# Motor_Driver_ClearanceIssues.net
KiCad netlist of a schematic drawn in EAGLE
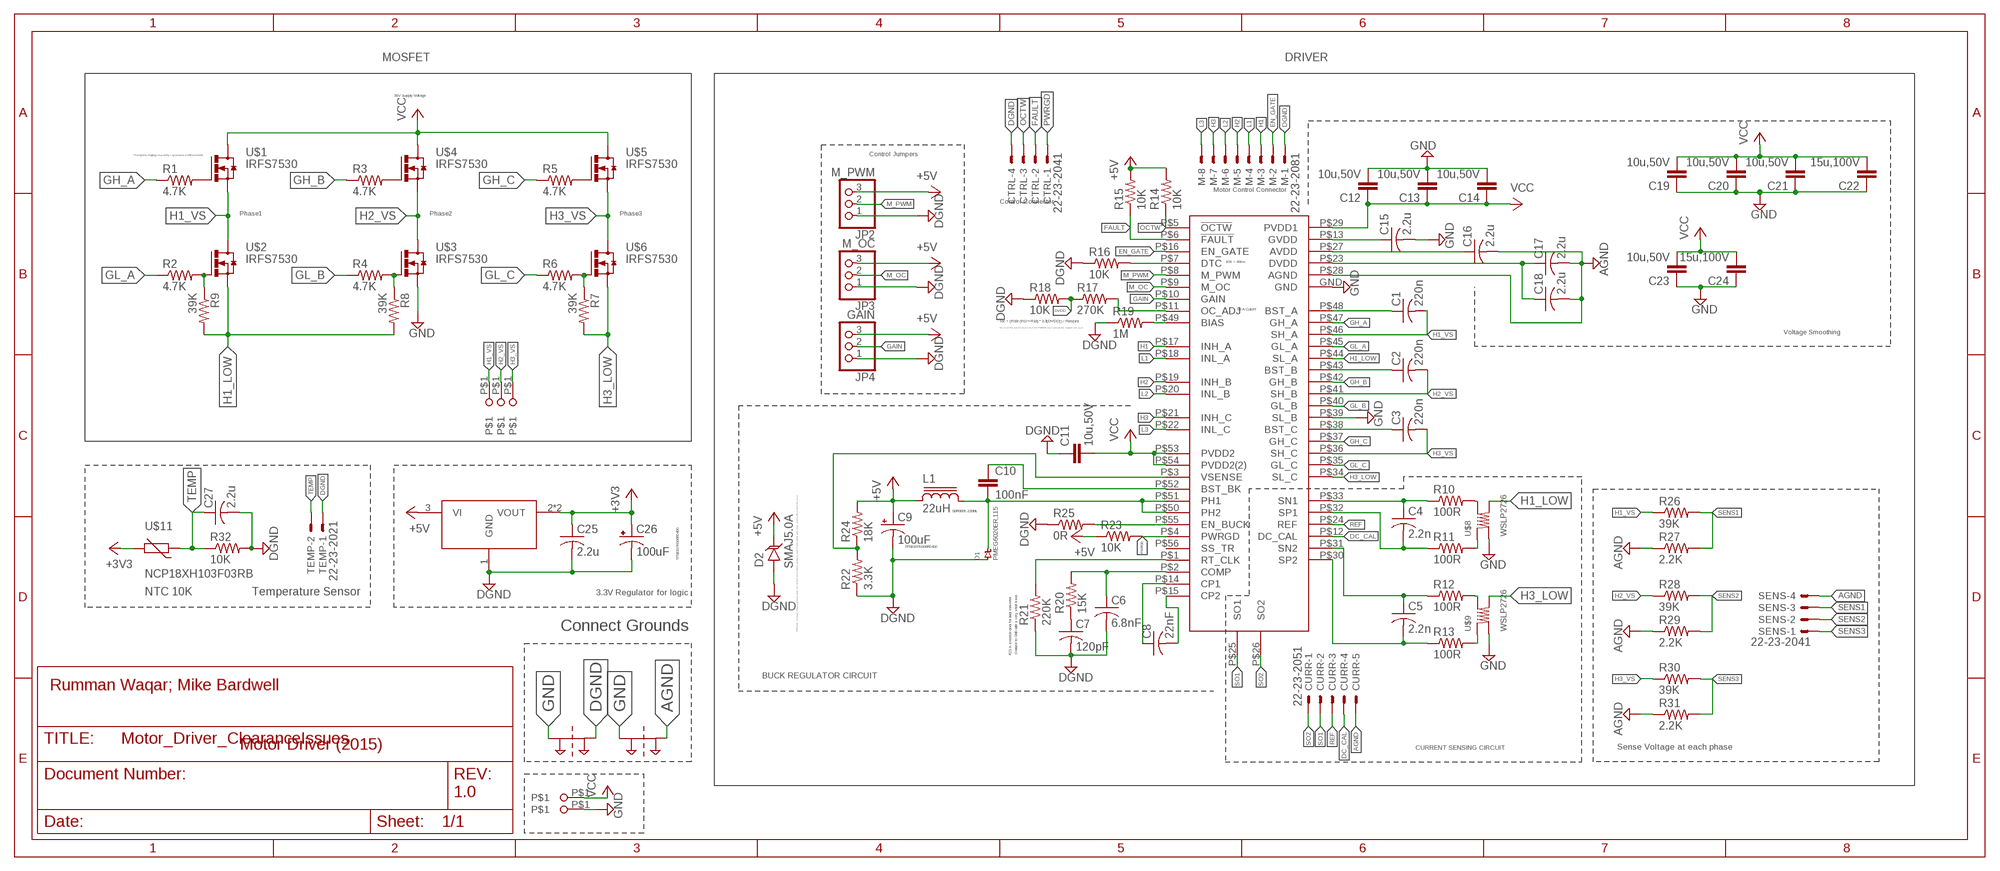
[diagram p0: schematic, sheet 1]

(export (version "E")
  (design (tool "Eeschema 10.0.6"))
  (components
    (comp (ref "C1")
      (value "220n")
      (footprint "eagle-import:C0805")
      (libsource (lib "eagle-import") (part "C-USC0805"))
    )
    (comp (ref "C2")
      (value "220n")
      (footprint "eagle-import:C0805")
      (libsource (lib "eagle-import") (part "C-USC0805"))
    )
    (comp (ref "C3")
      (value "220n")
      (footprint "eagle-import:C0805")
      (libsource (lib "eagle-import") (part "C-USC0805"))
    )
    (comp (ref "C4")
      (value "2.2n")
      (footprint "eagle-import:C0603")
      (libsource (lib "eagle-import") (part "C-USC0603"))
    )
    (comp (ref "C5")
      (value "2.2n")
      (footprint "eagle-import:C0603")
      (libsource (lib "eagle-import") (part "C-USC0603"))
    )
    (comp (ref "C6")
      (value "6.8nF")
      (footprint "eagle-import:C0603")
      (libsource (lib "eagle-import") (part "C-USC0603"))
    )
    (comp (ref "C7")
      (value "120pF")
      (footprint "eagle-import:C0603")
      (libsource (lib "eagle-import") (part "C-USC0603"))
    )
    (comp (ref "C8")
      (value "22nF")
      (footprint "eagle-import:C0603")
      (libsource (lib "eagle-import") (part "C-USC0603"))
    )
    (comp (ref "C9")
      (value "100uF")
      (footprint "eagle-import:EIA3528-KIT")
      (libsource (lib "eagle-import") (part "CAP_POL3528-KIT"))
    )
    (comp (ref "C10")
      (value "100nF")
      (footprint "eagle-import:0805")
      (libsource (lib "eagle-import") (part "CAP0805"))
    )
    (comp (ref "C11")
      (value "10u,50V")
      (footprint "eagle-import:1206")
      (libsource (lib "eagle-import") (part "CAP1206"))
    )
    (comp (ref "C12")
      (value "10u,50V")
      (footprint "eagle-import:1206")
      (libsource (lib "eagle-import") (part "CAP1206"))
    )
    (comp (ref "C13")
      (value "10u,50V")
      (footprint "eagle-import:1206")
      (libsource (lib "eagle-import") (part "CAP1206"))
    )
    (comp (ref "C14")
      (value "10u,50V")
      (footprint "eagle-import:1206")
      (libsource (lib "eagle-import") (part "CAP1206"))
    )
    (comp (ref "C15")
      (value "2.2u")
      (footprint "eagle-import:C0805")
      (libsource (lib "eagle-import") (part "C-USC0805"))
    )
    (comp (ref "C16")
      (value "2.2u")
      (footprint "eagle-import:C0805")
      (libsource (lib "eagle-import") (part "C-USC0805"))
    )
    (comp (ref "C17")
      (value "2.2u")
      (footprint "eagle-import:C0805")
      (libsource (lib "eagle-import") (part "C-USC0805"))
    )
    (comp (ref "C18")
      (value "2.2u")
      (footprint "eagle-import:C0805")
      (libsource (lib "eagle-import") (part "C-USC0805"))
    )
    (comp (ref "C19")
      (value "10u,50V")
      (footprint "eagle-import:1206")
      (libsource (lib "eagle-import") (part "CAP1206"))
    )
    (comp (ref "C20")
      (value "10u,50V")
      (footprint "eagle-import:1206")
      (libsource (lib "eagle-import") (part "CAP1206"))
    )
    (comp (ref "C21")
      (value "10u,50V")
      (footprint "eagle-import:1206")
      (libsource (lib "eagle-import") (part "CAP1206"))
    )
    (comp (ref "C22")
      (value "15u,100V")
      (footprint "eagle-import:C2220K")
      (libsource (lib "eagle-import") (part "C-EUC2220K"))
    )
    (comp (ref "C23")
      (value "10u,50V")
      (footprint "eagle-import:1206")
      (libsource (lib "eagle-import") (part "CAP1206"))
    )
    (comp (ref "C24")
      (value "15u,100V")
      (footprint "eagle-import:C2220K")
      (libsource (lib "eagle-import") (part "C-EUC2220K"))
    )
    (comp (ref "C25")
      (value "2.2u")
      (footprint "eagle-import:C0805")
      (libsource (lib "eagle-import") (part "C-USC0805"))
    )
    (comp (ref "C26")
      (value "100uF")
      (footprint "eagle-import:EIA3528-KIT")
      (libsource (lib "eagle-import") (part "CAP_POL3528-KIT"))
    )
    (comp (ref "C27")
      (value "2.2u")
      (footprint "eagle-import:C0805")
      (libsource (lib "eagle-import") (part "C-USC0805"))
    )
    (comp (ref "CTRL")
      (value "22-23-2041")
      (footprint "eagle-import:22-23-2041")
      (fields (field (name "MF") "MOLEX"))
      (libsource (lib "eagle-import") (part "22-23-2041"))
    )
    (comp (ref "CURR")
      (value "22-23-2051")
      (footprint "eagle-import:22-23-2051")
      (fields (field (name "MF") "MOLEX"))
      (libsource (lib "eagle-import") (part "22-23-2051"))
    )
    (comp (ref "D1")
      (value "PMEG6020ER,115")
      (footprint "eagle-import:SOD123W")
      (libsource (lib "eagle-import") (part "DIODE[SCHOTKY]-SOD123W"))
    )
    (comp (ref "D2")
      (value "SMAJ5.0A")
      (footprint "eagle-import:SMA-DIODE")
      (libsource (lib "eagle-import") (part "TVSSMA"))
    )
    (comp (ref "JP2")
      (value "M_PWM")
      (footprint "eagle-import:1X03")
      (libsource (lib "eagle-import") (part "PINHD-1X3"))
    )
    (comp (ref "JP3")
      (value "M_OC")
      (footprint "eagle-import:1X03")
      (libsource (lib "eagle-import") (part "PINHD-1X3"))
    )
    (comp (ref "JP4")
      (value "GAIN")
      (footprint "eagle-import:1X03")
      (libsource (lib "eagle-import") (part "PINHD-1X3"))
    )
    (comp (ref "L1")
      (value "22uH")
      (footprint "eagle-import:SDR0805")
      (libsource (lib "eagle-import") (part "SDR0805"))
    )
    (comp (ref "M")
      (value "22-23-2081")
      (footprint "eagle-import:22-23-2081")
      (fields (field (name "MF") "MOLEX"))
      (libsource (lib "eagle-import") (part "22-23-2081"))
    )
    (comp (ref "PT1")
      (value "2PT_GND_TIE")
      (footprint "eagle-import:2PT_GND_TIE")
      (libsource (lib "eagle-import") (part "2PT_GND_TIE"))
    )
    (comp (ref "PT2")
      (value "2PT_GND_TIE")
      (footprint "eagle-import:2PT_GND_TIE")
      (libsource (lib "eagle-import") (part "2PT_GND_TIE"))
    )
    (comp (ref "R1")
      (value "4.7K")
      (footprint "eagle-import:R0603")
      (libsource (lib "eagle-import") (part "R-US_R0603"))
    )
    (comp (ref "R2")
      (value "4.7K")
      (footprint "eagle-import:R0603")
      (libsource (lib "eagle-import") (part "R-US_R0603"))
    )
    (comp (ref "R3")
      (value "4.7K")
      (footprint "eagle-import:R0603")
      (libsource (lib "eagle-import") (part "R-US_R0603"))
    )
    (comp (ref "R4")
      (value "4.7K")
      (footprint "eagle-import:R0603")
      (libsource (lib "eagle-import") (part "R-US_R0603"))
    )
    (comp (ref "R5")
      (value "4.7K")
      (footprint "eagle-import:R0603")
      (libsource (lib "eagle-import") (part "R-US_R0603"))
    )
    (comp (ref "R6")
      (value "4.7K")
      (footprint "eagle-import:R0603")
      (libsource (lib "eagle-import") (part "R-US_R0603"))
    )
    (comp (ref "R7")
      (value "39K")
      (footprint "eagle-import:R0603")
      (libsource (lib "eagle-import") (part "R-US_R0603"))
    )
    (comp (ref "R8")
      (value "39K")
      (footprint "eagle-import:R0603")
      (libsource (lib "eagle-import") (part "R-US_R0603"))
    )
    (comp (ref "R9")
      (value "39K")
      (footprint "eagle-import:R0603")
      (libsource (lib "eagle-import") (part "R-US_R0603"))
    )
    (comp (ref "R10")
      (value "100R")
      (footprint "eagle-import:R0603")
      (libsource (lib "eagle-import") (part "R-US_R0603"))
    )
    (comp (ref "R11")
      (value "100R")
      (footprint "eagle-import:R0603")
      (libsource (lib "eagle-import") (part "R-US_R0603"))
    )
    (comp (ref "R12")
      (value "100R")
      (footprint "eagle-import:R0603")
      (libsource (lib "eagle-import") (part "R-US_R0603"))
    )
    (comp (ref "R13")
      (value "100R")
      (footprint "eagle-import:R0603")
      (libsource (lib "eagle-import") (part "R-US_R0603"))
    )
    (comp (ref "R14")
      (value "10K")
      (footprint "eagle-import:R0603")
      (libsource (lib "eagle-import") (part "R-US_R0603"))
    )
    (comp (ref "R15")
      (value "10K")
      (footprint "eagle-import:R0603")
      (libsource (lib "eagle-import") (part "R-US_R0603"))
    )
    (comp (ref "R16")
      (value "10K")
      (footprint "eagle-import:R0603")
      (libsource (lib "eagle-import") (part "R-US_R0603"))
    )
    (comp (ref "R17")
      (value "270K")
      (footprint "eagle-import:R0603")
      (libsource (lib "eagle-import") (part "R-US_R0603"))
    )
    (comp (ref "R18")
      (value "10K")
      (footprint "eagle-import:R0603")
      (libsource (lib "eagle-import") (part "R-US_R0603"))
    )
    (comp (ref "R19")
      (value "1M")
      (footprint "eagle-import:R0603")
      (libsource (lib "eagle-import") (part "R-US_R0603"))
    )
    (comp (ref "R20")
      (value "15K")
      (footprint "eagle-import:R0603")
      (libsource (lib "eagle-import") (part "R-US_R0603"))
    )
    (comp (ref "R21")
      (value "220K")
      (footprint "eagle-import:R0603")
      (libsource (lib "eagle-import") (part "R-US_R0603"))
    )
    (comp (ref "R22")
      (value "3.3K")
      (footprint "eagle-import:R0603")
      (libsource (lib "eagle-import") (part "R-US_R0603"))
    )
    (comp (ref "R23")
      (value "10K")
      (footprint "eagle-import:R0603")
      (libsource (lib "eagle-import") (part "R-US_R0603"))
    )
    (comp (ref "R24")
      (value "18K")
      (footprint "eagle-import:R0603")
      (libsource (lib "eagle-import") (part "R-US_R0603"))
    )
    (comp (ref "R25")
      (value "0R")
      (footprint "eagle-import:R0603")
      (libsource (lib "eagle-import") (part "R-US_R0603"))
    )
    (comp (ref "R26")
      (value "39K")
      (footprint "eagle-import:R0805")
      (libsource (lib "eagle-import") (part "R-US_R0805"))
    )
    (comp (ref "R27")
      (value "2.2K")
      (footprint "eagle-import:R0805")
      (libsource (lib "eagle-import") (part "R-US_R0805"))
    )
    (comp (ref "R28")
      (value "39K")
      (footprint "eagle-import:R0805")
      (libsource (lib "eagle-import") (part "R-US_R0805"))
    )
    (comp (ref "R29")
      (value "2.2K")
      (footprint "eagle-import:R0805")
      (libsource (lib "eagle-import") (part "R-US_R0805"))
    )
    (comp (ref "R30")
      (value "39K")
      (footprint "eagle-import:R0805")
      (libsource (lib "eagle-import") (part "R-US_R0805"))
    )
    (comp (ref "R31")
      (value "2.2K")
      (footprint "eagle-import:R0805")
      (libsource (lib "eagle-import") (part "R-US_R0805"))
    )
    (comp (ref "R32")
      (value "10K")
      (footprint "eagle-import:M0805")
      (libsource (lib "eagle-import") (part "R-US_M0805"))
    )
    (comp (ref "SENS")
      (value "22-23-2041")
      (footprint "eagle-import:22-23-2041")
      (fields (field (name "MF") "MOLEX"))
      (libsource (lib "eagle-import") (part "22-23-2041"))
    )
    (comp (ref "TEMP")
      (value "22-23-2021")
      (footprint "eagle-import:22-23-2021")
      (fields (field (name "MF") "MOLEX"))
      (libsource (lib "eagle-import") (part "22-23-2021"))
    )
    (comp (ref "U$1")
      (value "IRFS7530")
      (footprint "eagle-import:IRF7530_HEATSINK")
      (libsource (lib "eagle-import") (part "IRFS7530_HEATSINK"))
    )
    (comp (ref "U$2")
      (value "IRFS7530")
      (footprint "eagle-import:IRF7530_HEATSINK")
      (libsource (lib "eagle-import") (part "IRFS7530_HEATSINK"))
    )
    (comp (ref "U$3")
      (value "IRFS7530")
      (footprint "eagle-import:IRF7530_HEATSINK")
      (libsource (lib "eagle-import") (part "IRFS7530_HEATSINK"))
    )
    (comp (ref "U$4")
      (value "IRFS7530")
      (footprint "eagle-import:IRF7530_HEATSINK")
      (libsource (lib "eagle-import") (part "IRFS7530_HEATSINK"))
    )
    (comp (ref "U$5")
      (value "IRFS7530")
      (footprint "eagle-import:IRF7530_HEATSINK")
      (libsource (lib "eagle-import") (part "IRFS7530_HEATSINK"))
    )
    (comp (ref "U$6")
      (value "IRFS7530")
      (footprint "eagle-import:IRF7530_HEATSINK")
      (libsource (lib "eagle-import") (part "IRFS7530_HEATSINK"))
    )
    (comp (ref "U$7")
      (value "DRV8302")
      (footprint "eagle-import:DRV8302")
      (libsource (lib "eagle-import") (part "DRV8302"))
    )
    (comp (ref "U$8")
      (value "WSLP2726")
      (footprint "eagle-import:WSLP2726")
      (libsource (lib "eagle-import") (part "WSLP2726"))
    )
    (comp (ref "U$9")
      (value "WSLP2726")
      (footprint "eagle-import:WSLP2726")
      (libsource (lib "eagle-import") (part "WSLP2726"))
    )
    (comp (ref "U$10")
      (value "TC2117")
      (footprint "eagle-import:SOT223")
      (libsource (lib "eagle-import") (part "TC2117"))
    )
    (comp (ref "U$11")
      (value "NCP18XH103F03RB")
      (footprint "eagle-import:R0603")
      (libsource (lib "eagle-import") (part "NCP18XH103F03RB"))
    )
    (comp (ref "U$12")
      (value "1CONN_SOLDER")
      (footprint "eagle-import:1CONN_PAD")
      (libsource (lib "eagle-import") (part "1CONN_SOLDER"))
    )
    (comp (ref "U$13")
      (value "1CONN_SOLDER")
      (footprint "eagle-import:1CONN_PAD")
      (libsource (lib "eagle-import") (part "1CONN_SOLDER"))
    )
    (comp (ref "U$14")
      (value "1CONN_SOLDER")
      (footprint "eagle-import:1CONN_PAD")
      (libsource (lib "eagle-import") (part "1CONN_SOLDER"))
    )
    (comp (ref "U$15")
      (value "1CONN_SOLDER")
      (footprint "eagle-import:1CONN_PAD")
      (libsource (lib "eagle-import") (part "1CONN_SOLDER"))
    )
    (comp (ref "U$16")
      (value "1CONN_SOLDER")
      (footprint "eagle-import:1CONN_PAD")
      (libsource (lib "eagle-import") (part "1CONN_SOLDER"))
    )
  )
  (nets
    (net (code "1") (name "+3V3") (class "Default")
      (node (ref "C25") (pin "1") (pinfunction "1_1") (pintype "passive"))
      (node (ref "C26") (pin "A") (pinfunction "+_A") (pintype "passive"))
      (node (ref "U$10") (pin "2") (pinfunction "VOUT_2") (pintype "bidirectional"))
      (node (ref "U$10") (pin "4") (pinfunction "VOUT_4") (pintype "bidirectional"))
      (node (ref "U$11") (pin "2") (pinfunction "2_2") (pintype "passive"))
    )
    (net (code "2") (name "+5V") (class "Default")
      (node (ref "C9") (pin "A") (pinfunction "+_A") (pintype "passive"))
      (node (ref "D2") (pin "C") (pinfunction "C_C") (pintype "passive"))
      (node (ref "JP2") (pin "3") (pinfunction "3_3") (pintype "passive"))
      (node (ref "JP3") (pin "3") (pinfunction "3_3") (pintype "passive"))
      (node (ref "JP4") (pin "3") (pinfunction "3_3") (pintype "passive"))
      (node (ref "L1") (pin "1") (pinfunction "1_1") (pintype "passive"))
      (node (ref "R14") (pin "2") (pinfunction "2_2") (pintype "passive"))
      (node (ref "R15") (pin "2") (pinfunction "2_2") (pintype "passive"))
      (node (ref "R23") (pin "1") (pinfunction "1_1") (pintype "passive"))
      (node (ref "R24") (pin "2") (pinfunction "2_2") (pintype "passive"))
      (node (ref "U$10") (pin "3") (pinfunction "VI_3") (pintype "bidirectional"))
    )
    (net (code "3") (name "AGND") (class "Default")
      (node (ref "C16") (pin "2") (pinfunction "2_2") (pintype "passive"))
      (node (ref "C17") (pin "2") (pinfunction "2_2") (pintype "passive"))
      (node (ref "C18") (pin "2") (pinfunction "2_2") (pintype "passive"))
      (node (ref "CURR") (pin "5") (pinfunction "S_5") (pintype "passive"))
      (node (ref "PT2") (pin "P$2") (pinfunction "P$2_P$2") (pintype "bidirectional"))
      (node (ref "R27") (pin "1") (pinfunction "1_1") (pintype "passive"))
      (node (ref "R29") (pin "1") (pinfunction "1_1") (pintype "passive"))
      (node (ref "R31") (pin "1") (pinfunction "1_1") (pintype "passive"))
      (node (ref "SENS") (pin "4") (pinfunction "S_4") (pintype "passive"))
      (node (ref "U$7") (pin "P$28") (pinfunction "AGND_P$28") (pintype "bidirectional"))
    )
    (net (code "4") (name "DC_CAL") (class "Default")
      (node (ref "CURR") (pin "4") (pinfunction "S_4") (pintype "passive"))
      (node (ref "U$7") (pin "P$12") (pinfunction "DC_CAL_P$12") (pintype "bidirectional"))
    )
    (net (code "5") (name "DGND") (class "Default")
      (node (ref "C11") (pin "1") (pinfunction "1_1") (pintype "passive"))
      (node (ref "C25") (pin "2") (pinfunction "2_2") (pintype "passive"))
      (node (ref "C26") (pin "C") (pinfunction "-_C") (pintype "passive"))
      (node (ref "C27") (pin "2") (pinfunction "2_2") (pintype "passive"))
      (node (ref "C6") (pin "2") (pinfunction "2_2") (pintype "passive"))
      (node (ref "C7") (pin "2") (pinfunction "2_2") (pintype "passive"))
      (node (ref "C9") (pin "C") (pinfunction "-_C") (pintype "passive"))
      (node (ref "CTRL") (pin "4") (pinfunction "S_4") (pintype "passive"))
      (node (ref "D1") (pin "P$1") (pinfunction "1_P$1") (pintype "bidirectional"))
      (node (ref "D2") (pin "A") (pinfunction "A_A") (pintype "passive"))
      (node (ref "JP2") (pin "1") (pinfunction "1_1") (pintype "passive"))
      (node (ref "JP3") (pin "1") (pinfunction "1_1") (pintype "passive"))
      (node (ref "JP4") (pin "1") (pinfunction "1_1") (pintype "passive"))
      (node (ref "M") (pin "1") (pinfunction "S_1") (pintype "passive"))
      (node (ref "PT1") (pin "P$2") (pinfunction "P$2_P$2") (pintype "bidirectional"))
      (node (ref "R16") (pin "1") (pinfunction "1_1") (pintype "passive"))
      (node (ref "R18") (pin "1") (pinfunction "1_1") (pintype "passive"))
      (node (ref "R19") (pin "1") (pinfunction "1_1") (pintype "passive"))
      (node (ref "R21") (pin "1") (pinfunction "1_1") (pintype "passive"))
      (node (ref "R22") (pin "1") (pinfunction "1_1") (pintype "passive"))
      (node (ref "R25") (pin "1") (pinfunction "1_1") (pintype "passive"))
      (node (ref "R32") (pin "2") (pinfunction "2_2") (pintype "passive"))
      (node (ref "TEMP") (pin "1") (pinfunction "S_1") (pintype "passive"))
      (node (ref "U$10") (pin "1") (pinfunction "GND_1") (pintype "bidirectional"))
    )
    (net (code "6") (name "DVDD") (class "Default")
      (node (ref "R17") (pin "1") (pinfunction "1_1") (pintype "passive"))
      (node (ref "R18") (pin "2") (pinfunction "2_2") (pintype "passive"))
    )
    (net (code "7") (name "EN_GATE") (class "Default")
      (node (ref "M") (pin "2") (pinfunction "S_2") (pintype "passive"))
      (node (ref "U$7") (pin "P$16") (pinfunction "EN_GATE_P$16") (pintype "bidirectional"))
    )
    (net (code "8") (name "FAULT") (class "Default")
      (node (ref "CTRL") (pin "2") (pinfunction "S_2") (pintype "passive"))
      (node (ref "R15") (pin "1") (pinfunction "1_1") (pintype "passive"))
      (node (ref "U$7") (pin "P$6") (pinfunction "~{FAULT}_P$6") (pintype "bidirectional"))
    )
    (net (code "9") (name "GAIN") (class "Default")
      (node (ref "JP4") (pin "2") (pinfunction "2_2") (pintype "passive"))
      (node (ref "U$7") (pin "P$10") (pinfunction "GAIN_P$10") (pintype "bidirectional"))
    )
    (net (code "10") (name "GH_A") (class "Default")
      (node (ref "R1") (pin "1") (pinfunction "1_1") (pintype "passive"))
      (node (ref "U$7") (pin "P$47") (pinfunction "GH_A_P$47") (pintype "bidirectional"))
    )
    (net (code "11") (name "GH_B") (class "Default")
      (node (ref "R3") (pin "1") (pinfunction "1_1") (pintype "passive"))
      (node (ref "U$7") (pin "P$42") (pinfunction "GH_B_P$42") (pintype "bidirectional"))
    )
    (net (code "12") (name "GH_C") (class "Default")
      (node (ref "R5") (pin "1") (pinfunction "1_1") (pintype "passive"))
      (node (ref "U$7") (pin "P$37") (pinfunction "GH_C_P$37") (pintype "bidirectional"))
    )
    (net (code "13") (name "GL_A") (class "Default")
      (node (ref "R2") (pin "1") (pinfunction "1_1") (pintype "passive"))
      (node (ref "U$7") (pin "P$45") (pinfunction "GL_A_P$45") (pintype "bidirectional"))
    )
    (net (code "14") (name "GL_B") (class "Default")
      (node (ref "R4") (pin "1") (pinfunction "1_1") (pintype "passive"))
      (node (ref "U$7") (pin "P$40") (pinfunction "GL_B_P$40") (pintype "bidirectional"))
    )
    (net (code "15") (name "GL_C") (class "Default")
      (node (ref "R6") (pin "1") (pinfunction "1_1") (pintype "passive"))
      (node (ref "U$7") (pin "P$35") (pinfunction "GL_C_P$35") (pintype "bidirectional"))
    )
    (net (code "16") (name "GND") (class "Default")
      (node (ref "C12") (pin "2") (pinfunction "2_2") (pintype "passive"))
      (node (ref "C13") (pin "2") (pinfunction "2_2") (pintype "passive"))
      (node (ref "C14") (pin "2") (pinfunction "2_2") (pintype "passive"))
      (node (ref "C15") (pin "2") (pinfunction "2_2") (pintype "passive"))
      (node (ref "C19") (pin "1") (pinfunction "1_1") (pintype "passive"))
      (node (ref "C20") (pin "1") (pinfunction "1_1") (pintype "passive"))
      (node (ref "C21") (pin "1") (pinfunction "1_1") (pintype "passive"))
      (node (ref "C22") (pin "1") (pinfunction "1_1") (pintype "passive"))
      (node (ref "C23") (pin "1") (pinfunction "1_1") (pintype "passive"))
      (node (ref "C24") (pin "1") (pinfunction "1_1") (pintype "passive"))
      (node (ref "PT1") (pin "P$1") (pinfunction "P$1_P$1") (pintype "bidirectional"))
      (node (ref "PT2") (pin "P$1") (pinfunction "P$1_P$1") (pintype "bidirectional"))
      (node (ref "U$16") (pin "P$1") (pinfunction "P$1_P$1") (pintype "bidirectional"))
      (node (ref "U$3") (pin "S1") (pinfunction "S_S1") (pintype "passive"))
      (node (ref "U$3") (pin "S2") (pinfunction "S_S2") (pintype "passive"))
      (node (ref "U$3") (pin "S3") (pinfunction "S_S3") (pintype "passive"))
      (node (ref "U$3") (pin "S4") (pinfunction "S_S4") (pintype "passive"))
      (node (ref "U$3") (pin "S5") (pinfunction "S_S5") (pintype "passive"))
      (node (ref "U$7") (pin "GND") (pinfunction "GND_GND") (pintype "bidirectional"))
      (node (ref "U$7") (pin "P$39") (pinfunction "SL_B_P$39") (pintype "bidirectional"))
      (node (ref "U$8") (pin "P$2") (pinfunction "P$2_P$2") (pintype "bidirectional"))
      (node (ref "U$9") (pin "P$2") (pinfunction "P$2_P$2") (pintype "bidirectional"))
    )
    (net (code "17") (name "H1") (class "Default")
      (node (ref "M") (pin "3") (pinfunction "S_3") (pintype "passive"))
      (node (ref "U$7") (pin "P$17") (pinfunction "INH_A_P$17") (pintype "bidirectional"))
    )
    (net (code "18") (name "H1_LOW") (class "Default")
      (node (ref "R8") (pin "2") (pinfunction "2_2") (pintype "passive"))
      (node (ref "R9") (pin "2") (pinfunction "2_2") (pintype "passive"))
      (node (ref "U$2") (pin "S1") (pinfunction "S_S1") (pintype "passive"))
      (node (ref "U$2") (pin "S2") (pinfunction "S_S2") (pintype "passive"))
      (node (ref "U$2") (pin "S3") (pinfunction "S_S3") (pintype "passive"))
      (node (ref "U$2") (pin "S4") (pinfunction "S_S4") (pintype "passive"))
      (node (ref "U$2") (pin "S5") (pinfunction "S_S5") (pintype "passive"))
      (node (ref "U$7") (pin "P$44") (pinfunction "SL_A_P$44") (pintype "bidirectional"))
      (node (ref "U$8") (pin "P$1") (pinfunction "P$1_P$1") (pintype "bidirectional"))
    )
    (net (code "19") (name "H1_VS") (class "Default")
      (node (ref "C1") (pin "2") (pinfunction "2_2") (pintype "passive"))
      (node (ref "R26") (pin "1") (pinfunction "1_1") (pintype "passive"))
      (node (ref "U$1") (pin "S1") (pinfunction "S_S1") (pintype "passive"))
      (node (ref "U$1") (pin "S2") (pinfunction "S_S2") (pintype "passive"))
      (node (ref "U$1") (pin "S3") (pinfunction "S_S3") (pintype "passive"))
      (node (ref "U$1") (pin "S4") (pinfunction "S_S4") (pintype "passive"))
      (node (ref "U$1") (pin "S5") (pinfunction "S_S5") (pintype "passive"))
      (node (ref "U$14") (pin "P$1") (pinfunction "P$1_P$1") (pintype "bidirectional"))
      (node (ref "U$2") (pin "D1") (pinfunction "D_D1") (pintype "passive"))
      (node (ref "U$7") (pin "P$46") (pinfunction "SH_A_P$46") (pintype "bidirectional"))
    )
    (net (code "20") (name "H2") (class "Default")
      (node (ref "M") (pin "5") (pinfunction "S_5") (pintype "passive"))
      (node (ref "U$7") (pin "P$19") (pinfunction "INH_B_P$19") (pintype "bidirectional"))
    )
    (net (code "21") (name "H2_VS") (class "Default")
      (node (ref "C2") (pin "2") (pinfunction "2_2") (pintype "passive"))
      (node (ref "R28") (pin "1") (pinfunction "1_1") (pintype "passive"))
      (node (ref "U$13") (pin "P$1") (pinfunction "P$1_P$1") (pintype "bidirectional"))
      (node (ref "U$3") (pin "D1") (pinfunction "D_D1") (pintype "passive"))
      (node (ref "U$4") (pin "S1") (pinfunction "S_S1") (pintype "passive"))
      (node (ref "U$4") (pin "S2") (pinfunction "S_S2") (pintype "passive"))
      (node (ref "U$4") (pin "S3") (pinfunction "S_S3") (pintype "passive"))
      (node (ref "U$4") (pin "S4") (pinfunction "S_S4") (pintype "passive"))
      (node (ref "U$4") (pin "S5") (pinfunction "S_S5") (pintype "passive"))
      (node (ref "U$7") (pin "P$41") (pinfunction "SH_B_P$41") (pintype "bidirectional"))
    )
    (net (code "22") (name "H3") (class "Default")
      (node (ref "M") (pin "7") (pinfunction "S_7") (pintype "passive"))
      (node (ref "U$7") (pin "P$21") (pinfunction "INH_C_P$21") (pintype "bidirectional"))
    )
    (net (code "23") (name "H3_LOW") (class "Default")
      (node (ref "R7") (pin "2") (pinfunction "2_2") (pintype "passive"))
      (node (ref "U$6") (pin "S1") (pinfunction "S_S1") (pintype "passive"))
      (node (ref "U$6") (pin "S2") (pinfunction "S_S2") (pintype "passive"))
      (node (ref "U$6") (pin "S3") (pinfunction "S_S3") (pintype "passive"))
      (node (ref "U$6") (pin "S4") (pinfunction "S_S4") (pintype "passive"))
      (node (ref "U$6") (pin "S5") (pinfunction "S_S5") (pintype "passive"))
      (node (ref "U$7") (pin "P$34") (pinfunction "SL_C_P$34") (pintype "bidirectional"))
      (node (ref "U$9") (pin "P$1") (pinfunction "P$1_P$1") (pintype "bidirectional"))
    )
    (net (code "24") (name "H3_VS") (class "Default")
      (node (ref "C3") (pin "2") (pinfunction "2_2") (pintype "passive"))
      (node (ref "R30") (pin "1") (pinfunction "1_1") (pintype "passive"))
      (node (ref "U$12") (pin "P$1") (pinfunction "P$1_P$1") (pintype "bidirectional"))
      (node (ref "U$5") (pin "S1") (pinfunction "S_S1") (pintype "passive"))
      (node (ref "U$5") (pin "S2") (pinfunction "S_S2") (pintype "passive"))
      (node (ref "U$5") (pin "S3") (pinfunction "S_S3") (pintype "passive"))
      (node (ref "U$5") (pin "S4") (pinfunction "S_S4") (pintype "passive"))
      (node (ref "U$5") (pin "S5") (pinfunction "S_S5") (pintype "passive"))
      (node (ref "U$6") (pin "D1") (pinfunction "D_D1") (pintype "passive"))
      (node (ref "U$7") (pin "P$36") (pinfunction "SH_C_P$36") (pintype "bidirectional"))
    )
    (net (code "25") (name "L1") (class "Default")
      (node (ref "M") (pin "4") (pinfunction "S_4") (pintype "passive"))
      (node (ref "U$7") (pin "P$18") (pinfunction "INL_A_P$18") (pintype "bidirectional"))
    )
    (net (code "26") (name "L2") (class "Default")
      (node (ref "M") (pin "6") (pinfunction "S_6") (pintype "passive"))
      (node (ref "U$7") (pin "P$20") (pinfunction "INL_B_P$20") (pintype "bidirectional"))
    )
    (net (code "27") (name "L3") (class "Default")
      (node (ref "M") (pin "8") (pinfunction "S_8") (pintype "passive"))
      (node (ref "U$7") (pin "P$22") (pinfunction "INL_C_P$22") (pintype "bidirectional"))
    )
    (net (code "28") (name "M_OC") (class "Default")
      (node (ref "JP3") (pin "2") (pinfunction "2_2") (pintype "passive"))
      (node (ref "U$7") (pin "P$9") (pinfunction "M_OC_P$9") (pintype "bidirectional"))
    )
    (net (code "29") (name "M_PWM") (class "Default")
      (node (ref "JP2") (pin "2") (pinfunction "2_2") (pintype "passive"))
      (node (ref "U$7") (pin "P$8") (pinfunction "M_PWM_P$8") (pintype "bidirectional"))
    )
    (net (code "30") (name "Net-(C7-Pad1)") (class "Default")
      (node (ref "C7") (pin "1") (pinfunction "1_1") (pintype "passive"))
      (node (ref "R20") (pin "1") (pinfunction "1_1") (pintype "passive"))
    )
    (net (code "31") (name "Net-(D1-2)") (class "Default")
      (node (ref "C10") (pin "2") (pinfunction "2_2") (pintype "passive"))
      (node (ref "D1") (pin "P$2") (pinfunction "2_P$2") (pintype "bidirectional"))
      (node (ref "L1") (pin "2") (pinfunction "2_2") (pintype "passive"))
      (node (ref "U$7") (pin "P$50") (pinfunction "PH2_P$50") (pintype "bidirectional"))
      (node (ref "U$7") (pin "P$51") (pinfunction "PH1_P$51") (pintype "bidirectional"))
    )
    (net (code "32") (name "Net-(R10-Pad2)") (class "Default")
      (node (ref "R10") (pin "2") (pinfunction "2_2") (pintype "passive"))
      (node (ref "U$8") (pin "P$3") (pinfunction "P$3_P$3") (pintype "bidirectional"))
    )
    (net (code "33") (name "Net-(R11-Pad2)") (class "Default")
      (node (ref "R11") (pin "2") (pinfunction "2_2") (pintype "passive"))
      (node (ref "U$8") (pin "P$4") (pinfunction "P$4_P$4") (pintype "bidirectional"))
    )
    (net (code "34") (name "Net-(R12-Pad2)") (class "Default")
      (node (ref "R12") (pin "2") (pinfunction "2_2") (pintype "passive"))
      (node (ref "U$9") (pin "P$3") (pinfunction "P$3_P$3") (pintype "bidirectional"))
    )
    (net (code "35") (name "Net-(R13-Pad2)") (class "Default")
      (node (ref "R13") (pin "2") (pinfunction "2_2") (pintype "passive"))
      (node (ref "U$9") (pin "P$4") (pinfunction "P$4_P$4") (pintype "bidirectional"))
    )
    (net (code "36") (name "Net-(U$1-G)") (class "Default")
      (node (ref "R1") (pin "2") (pinfunction "2_2") (pintype "passive"))
      (node (ref "U$1") (pin "G1") (pinfunction "G_G1") (pintype "passive"))
    )
    (net (code "37") (name "Net-(U$2-G)") (class "Default")
      (node (ref "R2") (pin "2") (pinfunction "2_2") (pintype "passive"))
      (node (ref "R9") (pin "1") (pinfunction "1_1") (pintype "passive"))
      (node (ref "U$2") (pin "G1") (pinfunction "G_G1") (pintype "passive"))
    )
    (net (code "38") (name "Net-(U$3-G)") (class "Default")
      (node (ref "R4") (pin "2") (pinfunction "2_2") (pintype "passive"))
      (node (ref "R8") (pin "1") (pinfunction "1_1") (pintype "passive"))
      (node (ref "U$3") (pin "G1") (pinfunction "G_G1") (pintype "passive"))
    )
    (net (code "39") (name "Net-(U$4-G)") (class "Default")
      (node (ref "R3") (pin "2") (pinfunction "2_2") (pintype "passive"))
      (node (ref "U$4") (pin "G1") (pinfunction "G_G1") (pintype "passive"))
    )
    (net (code "40") (name "Net-(U$5-G)") (class "Default")
      (node (ref "R5") (pin "2") (pinfunction "2_2") (pintype "passive"))
      (node (ref "U$5") (pin "G1") (pinfunction "G_G1") (pintype "passive"))
    )
    (net (code "41") (name "Net-(U$6-G)") (class "Default")
      (node (ref "R6") (pin "2") (pinfunction "2_2") (pintype "passive"))
      (node (ref "R7") (pin "1") (pinfunction "1_1") (pintype "passive"))
      (node (ref "U$6") (pin "G1") (pinfunction "G_G1") (pintype "passive"))
    )
    (net (code "42") (name "Net-(U$7-AVDD)") (class "Default")
      (node (ref "C16") (pin "1") (pinfunction "1_1") (pintype "passive"))
      (node (ref "U$7") (pin "P$27") (pinfunction "AVDD_P$27") (pintype "bidirectional"))
    )
    (net (code "43") (name "Net-(U$7-BIAS)") (class "Default")
      (node (ref "R19") (pin "2") (pinfunction "2_2") (pintype "passive"))
      (node (ref "U$7") (pin "P$49") (pinfunction "BIAS_P$49") (pintype "bidirectional"))
    )
    (net (code "44") (name "Net-(U$7-BST_A)") (class "Default")
      (node (ref "C1") (pin "1") (pinfunction "1_1") (pintype "passive"))
      (node (ref "U$7") (pin "P$48") (pinfunction "BST_A_P$48") (pintype "bidirectional"))
    )
    (net (code "45") (name "Net-(U$7-BST_B)") (class "Default")
      (node (ref "C2") (pin "1") (pinfunction "1_1") (pintype "passive"))
      (node (ref "U$7") (pin "P$43") (pinfunction "BST_B_P$43") (pintype "bidirectional"))
    )
    (net (code "46") (name "Net-(U$7-BST_BK)") (class "Default")
      (node (ref "C10") (pin "1") (pinfunction "1_1") (pintype "passive"))
      (node (ref "U$7") (pin "P$52") (pinfunction "BST_BK_P$52") (pintype "bidirectional"))
    )
    (net (code "47") (name "Net-(U$7-BST_C)") (class "Default")
      (node (ref "C3") (pin "1") (pinfunction "1_1") (pintype "passive"))
      (node (ref "U$7") (pin "P$38") (pinfunction "BST_C_P$38") (pintype "bidirectional"))
    )
    (net (code "48") (name "Net-(U$7-COMP)") (class "Default")
      (node (ref "C6") (pin "1") (pinfunction "1_1") (pintype "passive"))
      (node (ref "R20") (pin "2") (pinfunction "2_2") (pintype "passive"))
      (node (ref "U$7") (pin "P$2") (pinfunction "COMP_P$2") (pintype "bidirectional"))
    )
    (net (code "49") (name "Net-(U$7-CP1)") (class "Default")
      (node (ref "C8") (pin "1") (pinfunction "1_1") (pintype "passive"))
      (node (ref "U$7") (pin "P$14") (pinfunction "CP1_P$14") (pintype "bidirectional"))
    )
    (net (code "50") (name "Net-(U$7-CP2)") (class "Default")
      (node (ref "C8") (pin "2") (pinfunction "2_2") (pintype "passive"))
      (node (ref "U$7") (pin "P$15") (pinfunction "CP2_P$15") (pintype "bidirectional"))
    )
    (net (code "51") (name "Net-(U$7-DTC)") (class "Default")
      (node (ref "R16") (pin "2") (pinfunction "2_2") (pintype "passive"))
      (node (ref "U$7") (pin "P$7") (pinfunction "DTC_P$7") (pintype "bidirectional"))
    )
    (net (code "52") (name "Net-(U$7-DVDD)") (class "Default")
      (node (ref "C17") (pin "1") (pinfunction "1_1") (pintype "passive"))
      (node (ref "C18") (pin "1") (pinfunction "1_1") (pintype "passive"))
      (node (ref "U$7") (pin "P$23") (pinfunction "DVDD_P$23") (pintype "bidirectional"))
    )
    (net (code "53") (name "Net-(U$7-EN_BUCK)") (class "Default")
      (node (ref "R25") (pin "2") (pinfunction "2_2") (pintype "passive"))
      (node (ref "U$7") (pin "P$55") (pinfunction "EN_BUCK_P$55") (pintype "bidirectional"))
    )
    (net (code "54") (name "Net-(U$7-GVDD)") (class "Default")
      (node (ref "C15") (pin "1") (pinfunction "1_1") (pintype "passive"))
      (node (ref "U$7") (pin "P$13") (pinfunction "GVDD_P$13") (pintype "bidirectional"))
    )
    (net (code "55") (name "Net-(U$7-OC_ADJ)") (class "Default")
      (node (ref "R17") (pin "2") (pinfunction "2_2") (pintype "passive"))
      (node (ref "U$7") (pin "P$11") (pinfunction "OC_ADJ_P$11") (pintype "bidirectional"))
    )
    (net (code "56") (name "Net-(U$7-RT_CLK)") (class "Default")
      (node (ref "R21") (pin "2") (pinfunction "2_2") (pintype "passive"))
      (node (ref "U$7") (pin "P$1") (pinfunction "RT_CLK_P$1") (pintype "bidirectional"))
    )
    (net (code "57") (name "Net-(U$7-SN1)") (class "Default")
      (node (ref "C4") (pin "1") (pinfunction "1_1") (pintype "passive"))
      (node (ref "R10") (pin "1") (pinfunction "1_1") (pintype "passive"))
      (node (ref "U$7") (pin "P$33") (pinfunction "SN1_P$33") (pintype "bidirectional"))
    )
    (net (code "58") (name "Net-(U$7-SN2)") (class "Default")
      (node (ref "C5") (pin "1") (pinfunction "1_1") (pintype "passive"))
      (node (ref "R12") (pin "1") (pinfunction "1_1") (pintype "passive"))
      (node (ref "U$7") (pin "P$31") (pinfunction "SN2_P$31") (pintype "bidirectional"))
    )
    (net (code "59") (name "Net-(U$7-SP1)") (class "Default")
      (node (ref "C4") (pin "2") (pinfunction "2_2") (pintype "passive"))
      (node (ref "R11") (pin "1") (pinfunction "1_1") (pintype "passive"))
      (node (ref "U$7") (pin "P$32") (pinfunction "SP1_P$32") (pintype "bidirectional"))
    )
    (net (code "60") (name "Net-(U$7-SP2)") (class "Default")
      (node (ref "C5") (pin "2") (pinfunction "2_2") (pintype "passive"))
      (node (ref "R13") (pin "1") (pinfunction "1_1") (pintype "passive"))
      (node (ref "U$7") (pin "P$30") (pinfunction "SP2_P$30") (pintype "bidirectional"))
    )
    (net (code "61") (name "Net-(U$7-VSENSE)") (class "Default")
      (node (ref "R22") (pin "2") (pinfunction "2_2") (pintype "passive"))
      (node (ref "R24") (pin "1") (pinfunction "1_1") (pintype "passive"))
      (node (ref "U$7") (pin "P$3") (pinfunction "VSENSE_P$3") (pintype "bidirectional"))
    )
    (net (code "62") (name "OCTW") (class "Default")
      (node (ref "CTRL") (pin "3") (pinfunction "S_3") (pintype "passive"))
      (node (ref "R14") (pin "1") (pinfunction "1_1") (pintype "passive"))
      (node (ref "U$7") (pin "P$5") (pinfunction "~{OCTW}_P$5") (pintype "bidirectional"))
    )
    (net (code "63") (name "PWRGD") (class "Default")
      (node (ref "CTRL") (pin "1") (pinfunction "S_1") (pintype "passive"))
      (node (ref "R23") (pin "2") (pinfunction "2_2") (pintype "passive"))
      (node (ref "U$7") (pin "P$4") (pinfunction "PWRGD_P$4") (pintype "bidirectional"))
    )
    (net (code "64") (name "REF") (class "Default")
      (node (ref "CURR") (pin "3") (pinfunction "S_3") (pintype "passive"))
      (node (ref "U$7") (pin "P$24") (pinfunction "REF_P$24") (pintype "bidirectional"))
    )
    (net (code "65") (name "SENS1") (class "Default")
      (node (ref "R26") (pin "2") (pinfunction "2_2") (pintype "passive"))
      (node (ref "R27") (pin "2") (pinfunction "2_2") (pintype "passive"))
      (node (ref "SENS") (pin "3") (pinfunction "S_3") (pintype "passive"))
    )
    (net (code "66") (name "SENS2") (class "Default")
      (node (ref "R28") (pin "2") (pinfunction "2_2") (pintype "passive"))
      (node (ref "R29") (pin "2") (pinfunction "2_2") (pintype "passive"))
      (node (ref "SENS") (pin "2") (pinfunction "S_2") (pintype "passive"))
    )
    (net (code "67") (name "SENS3") (class "Default")
      (node (ref "R30") (pin "2") (pinfunction "2_2") (pintype "passive"))
      (node (ref "R31") (pin "2") (pinfunction "2_2") (pintype "passive"))
      (node (ref "SENS") (pin "1") (pinfunction "S_1") (pintype "passive"))
    )
    (net (code "68") (name "SO1") (class "Default")
      (node (ref "CURR") (pin "2") (pinfunction "S_2") (pintype "passive"))
      (node (ref "U$7") (pin "P$25") (pinfunction "SO1_P$25") (pintype "bidirectional"))
    )
    (net (code "69") (name "SO2") (class "Default")
      (node (ref "CURR") (pin "1") (pinfunction "S_1") (pintype "passive"))
      (node (ref "U$7") (pin "P$26") (pinfunction "SO2_P$26") (pintype "bidirectional"))
    )
    (net (code "70") (name "TEMP") (class "Default")
      (node (ref "C27") (pin "1") (pinfunction "1_1") (pintype "passive"))
      (node (ref "R32") (pin "1") (pinfunction "1_1") (pintype "passive"))
      (node (ref "TEMP") (pin "2") (pinfunction "S_2") (pintype "passive"))
      (node (ref "U$11") (pin "1") (pinfunction "1_1") (pintype "passive"))
    )
    (net (code "71") (name "VCC") (class "Default")
      (node (ref "C11") (pin "2") (pinfunction "2_2") (pintype "passive"))
      (node (ref "C12") (pin "1") (pinfunction "1_1") (pintype "passive"))
      (node (ref "C13") (pin "1") (pinfunction "1_1") (pintype "passive"))
      (node (ref "C14") (pin "1") (pinfunction "1_1") (pintype "passive"))
      (node (ref "C19") (pin "2") (pinfunction "2_2") (pintype "passive"))
      (node (ref "C20") (pin "2") (pinfunction "2_2") (pintype "passive"))
      (node (ref "C21") (pin "2") (pinfunction "2_2") (pintype "passive"))
      (node (ref "C22") (pin "2") (pinfunction "2_2") (pintype "passive"))
      (node (ref "C23") (pin "2") (pinfunction "2_2") (pintype "passive"))
      (node (ref "C24") (pin "2") (pinfunction "2_2") (pintype "passive"))
      (node (ref "U$1") (pin "D1") (pinfunction "D_D1") (pintype "passive"))
      (node (ref "U$15") (pin "P$1") (pinfunction "P$1_P$1") (pintype "bidirectional"))
      (node (ref "U$4") (pin "D1") (pinfunction "D_D1") (pintype "passive"))
      (node (ref "U$5") (pin "D1") (pinfunction "D_D1") (pintype "passive"))
      (node (ref "U$7") (pin "P$29") (pinfunction "PVDD1_P$29") (pintype "bidirectional"))
      (node (ref "U$7") (pin "P$53") (pinfunction "PVDD2_P$53") (pintype "bidirectional"))
      (node (ref "U$7") (pin "P$54") (pinfunction "PVDD2(2)_P$54") (pintype "bidirectional"))
    )
    (net (code "72") (name "unconnected-(U$7-SS_TR-PadP$56)") (class "Default")
      (node (ref "U$7") (pin "P$56") (pinfunction "SS_TR_P$56") (pintype "bidirectional"))
    )
  )
)
